# LedBoard.net
KiCad netlist of a schematic drawn in EAGLE
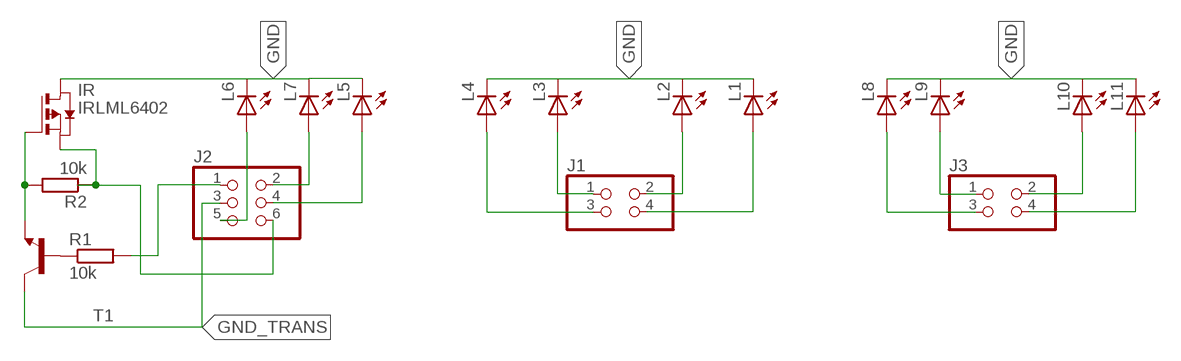
[diagram p0: schematic, sheet 1]

(export (version "E")
  (design (tool "Eeschema 10.0.6"))
  (components
    (comp (ref "IR")
      (value "IRLML6402")
      (footprint "eagle-import:SOT-23")
      (libsource (lib "eagle-import") (part "IRLML6402"))
    )
    (comp (ref "J1")
      (value "PINHD-2X2")
      (footprint "eagle-import:2X02")
      (libsource (lib "eagle-import") (part "PINHD-2X2"))
    )
    (comp (ref "J2")
      (value "PINHD-2X3")
      (footprint "eagle-import:2X03")
      (libsource (lib "eagle-import") (part "PINHD-2X3"))
    )
    (comp (ref "J3")
      (value "PINHD-2X2")
      (footprint "eagle-import:2X02")
      (libsource (lib "eagle-import") (part "PINHD-2X2"))
    )
    (comp (ref "L1")
      (value "LEDKA-3528ASYC")
      (footprint "eagle-import:KA-3528ASYC")
      (libsource (lib "eagle-import") (part "LEDKA-3528ASYC"))
    )
    (comp (ref "L2")
      (value "LEDKA-3528ASYC")
      (footprint "eagle-import:KA-3528ASYC")
      (libsource (lib "eagle-import") (part "LEDKA-3528ASYC"))
    )
    (comp (ref "L3")
      (value "LEDKA-3528ASYC")
      (footprint "eagle-import:KA-3528ASYC")
      (libsource (lib "eagle-import") (part "LEDKA-3528ASYC"))
    )
    (comp (ref "L4")
      (value "LEDKA-3528ASYC")
      (footprint "eagle-import:KA-3528ASYC")
      (libsource (lib "eagle-import") (part "LEDKA-3528ASYC"))
    )
    (comp (ref "L5")
      (value "LEDKA-3528ASYC")
      (footprint "eagle-import:KA-3528ASYC")
      (libsource (lib "eagle-import") (part "LEDKA-3528ASYC"))
    )
    (comp (ref "L6")
      (value "LEDKA-3528ASYC")
      (footprint "eagle-import:KA-3528ASYC")
      (libsource (lib "eagle-import") (part "LEDKA-3528ASYC"))
    )
    (comp (ref "L7")
      (value "LEDKA-3528ASYC")
      (footprint "eagle-import:KA-3528ASYC")
      (libsource (lib "eagle-import") (part "LEDKA-3528ASYC"))
    )
    (comp (ref "L8")
      (value "LEDKA-3528ASYC")
      (footprint "eagle-import:KA-3528ASYC")
      (libsource (lib "eagle-import") (part "LEDKA-3528ASYC"))
    )
    (comp (ref "L9")
      (value "LEDKA-3528ASYC")
      (footprint "eagle-import:KA-3528ASYC")
      (libsource (lib "eagle-import") (part "LEDKA-3528ASYC"))
    )
    (comp (ref "L10")
      (value "LEDKA-3528ASYC")
      (footprint "eagle-import:KA-3528ASYC")
      (libsource (lib "eagle-import") (part "LEDKA-3528ASYC"))
    )
    (comp (ref "L11")
      (value "LEDKA-3528ASYC")
      (footprint "eagle-import:KA-3528ASYC")
      (libsource (lib "eagle-import") (part "LEDKA-3528ASYC"))
    )
    (comp (ref "R1")
      (value "10k")
      (footprint "eagle-import:R1206")
      (libsource (lib "eagle-import") (part "R-EU_R1206"))
    )
    (comp (ref "R2")
      (value "10k")
      (footprint "eagle-import:R1206")
      (libsource (lib "eagle-import") (part "R-EU_R1206"))
    )
    (comp (ref "T1")
      (value "BC818-40-NPN-SOT23-BEC")
      (footprint "eagle-import:SOT23-BEC")
      (libsource (lib "eagle-import") (part "-NPN-SOT23-BECBC818-40"))
    )
  )
  (nets
    (net (code "1") (name "GND") (class "Default")
      (node (ref "IR") (pin "3") (pinfunction "D_3") (pintype "passive"))
      (node (ref "L1") (pin "C") (pinfunction "C_C") (pintype "passive"))
      (node (ref "L10") (pin "C") (pinfunction "C_C") (pintype "passive"))
      (node (ref "L11") (pin "C") (pinfunction "C_C") (pintype "passive"))
      (node (ref "L2") (pin "C") (pinfunction "C_C") (pintype "passive"))
      (node (ref "L3") (pin "C") (pinfunction "C_C") (pintype "passive"))
      (node (ref "L4") (pin "C") (pinfunction "C_C") (pintype "passive"))
      (node (ref "L5") (pin "C") (pinfunction "C_C") (pintype "passive"))
      (node (ref "L6") (pin "C") (pinfunction "C_C") (pintype "passive"))
      (node (ref "L7") (pin "C") (pinfunction "C_C") (pintype "passive"))
      (node (ref "L8") (pin "C") (pinfunction "C_C") (pintype "passive"))
      (node (ref "L9") (pin "C") (pinfunction "C_C") (pintype "passive"))
    )
    (net (code "2") (name "GND_TRANS") (class "Default")
      (node (ref "J2") (pin "3") (pinfunction "3_3") (pintype "passive"))
      (node (ref "T1") (pin "C") (pinfunction "C_C") (pintype "passive"))
    )
    (net (code "3") (name "Net-(IR-G)") (class "Default")
      (node (ref "IR") (pin "1") (pinfunction "G_1") (pintype "passive"))
      (node (ref "R2") (pin "2") (pinfunction "2_2") (pintype "passive"))
      (node (ref "T1") (pin "E") (pinfunction "E_E") (pintype "passive"))
    )
    (net (code "4") (name "Net-(IR-S)") (class "Default")
      (node (ref "IR") (pin "2") (pinfunction "S_2") (pintype "passive"))
      (node (ref "J2") (pin "6") (pinfunction "6_6") (pintype "passive"))
      (node (ref "R2") (pin "1") (pinfunction "1_1") (pintype "passive"))
    )
    (net (code "5") (name "Net-(J1-Pad1)") (class "Default")
      (node (ref "J1") (pin "1") (pinfunction "1_1") (pintype "passive"))
      (node (ref "L3") (pin "A") (pinfunction "A_A") (pintype "passive"))
    )
    (net (code "6") (name "Net-(J1-Pad2)") (class "Default")
      (node (ref "J1") (pin "2") (pinfunction "2_2") (pintype "passive"))
      (node (ref "L2") (pin "A") (pinfunction "A_A") (pintype "passive"))
    )
    (net (code "7") (name "Net-(J1-Pad3)") (class "Default")
      (node (ref "J1") (pin "3") (pinfunction "3_3") (pintype "passive"))
      (node (ref "L4") (pin "A") (pinfunction "A_A") (pintype "passive"))
    )
    (net (code "8") (name "Net-(J1-Pad4)") (class "Default")
      (node (ref "J1") (pin "4") (pinfunction "4_4") (pintype "passive"))
      (node (ref "L1") (pin "A") (pinfunction "A_A") (pintype "passive"))
    )
    (net (code "9") (name "Net-(J2-Pad1)") (class "Default")
      (node (ref "J2") (pin "1") (pinfunction "1_1") (pintype "passive"))
      (node (ref "R1") (pin "2") (pinfunction "2_2") (pintype "passive"))
    )
    (net (code "10") (name "Net-(J2-Pad2)") (class "Default")
      (node (ref "J2") (pin "2") (pinfunction "2_2") (pintype "passive"))
      (node (ref "L7") (pin "A") (pinfunction "A_A") (pintype "passive"))
    )
    (net (code "11") (name "Net-(J2-Pad4)") (class "Default")
      (node (ref "J2") (pin "4") (pinfunction "4_4") (pintype "passive"))
      (node (ref "L5") (pin "A") (pinfunction "A_A") (pintype "passive"))
    )
    (net (code "12") (name "Net-(J2-Pad5)") (class "Default")
      (node (ref "J2") (pin "5") (pinfunction "5_5") (pintype "passive"))
      (node (ref "L6") (pin "A") (pinfunction "A_A") (pintype "passive"))
    )
    (net (code "13") (name "Net-(J3-Pad1)") (class "Default")
      (node (ref "J3") (pin "1") (pinfunction "1_1") (pintype "passive"))
      (node (ref "L9") (pin "A") (pinfunction "A_A") (pintype "passive"))
    )
    (net (code "14") (name "Net-(J3-Pad2)") (class "Default")
      (node (ref "J3") (pin "2") (pinfunction "2_2") (pintype "passive"))
      (node (ref "L10") (pin "A") (pinfunction "A_A") (pintype "passive"))
    )
    (net (code "15") (name "Net-(J3-Pad3)") (class "Default")
      (node (ref "J3") (pin "3") (pinfunction "3_3") (pintype "passive"))
      (node (ref "L8") (pin "A") (pinfunction "A_A") (pintype "passive"))
    )
    (net (code "16") (name "Net-(J3-Pad4)") (class "Default")
      (node (ref "J3") (pin "4") (pinfunction "4_4") (pintype "passive"))
      (node (ref "L11") (pin "A") (pinfunction "A_A") (pintype "passive"))
    )
    (net (code "17") (name "Net-(R1-Pad1)") (class "Default")
      (node (ref "R1") (pin "1") (pinfunction "1_1") (pintype "passive"))
      (node (ref "T1") (pin "B") (pinfunction "B_B") (pintype "passive"))
    )
  )
)
